# IC_Adapter_2x1x24.net
KiCad netlist of a schematic drawn in EAGLE
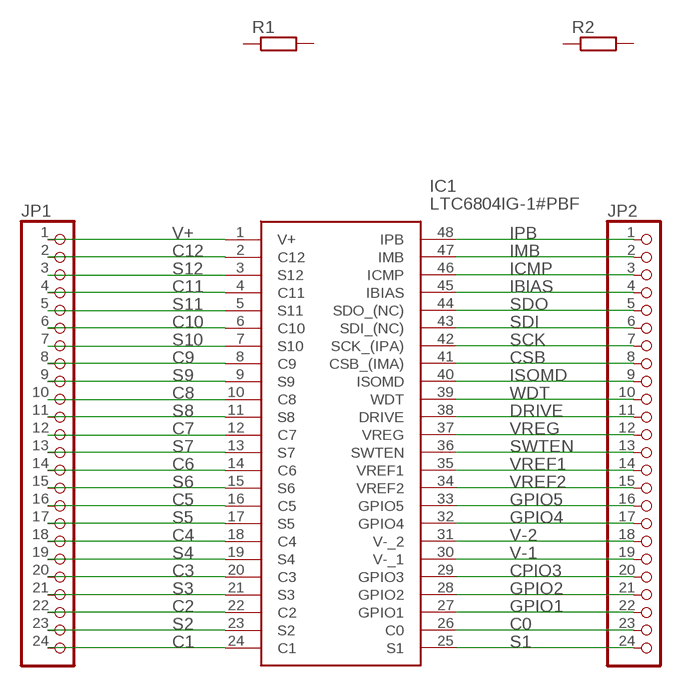
[diagram p0: schematic, sheet 1]

(export (version "E")
  (design (tool "Eeschema 10.0.6"))
  (components
    (comp (ref "IC1")
      (value "LTC6804IG-1#PBF")
      (footprint "eagle-import:SOP50P780X200-48N")
      (fields (field (name "MOUSER_PART_NUMBER") "584-LTC6804IG-1#PBF"))
      (libsource (lib "eagle-import") (part "LTC6804IG-1#PBF"))
    )
    (comp (ref "JP1")
      (value "PINHD-1X24")
      (footprint "eagle-import:1X24")
      (libsource (lib "eagle-import") (part "PINHD-1X24"))
    )
    (comp (ref "JP2")
      (value "PINHD-1X24")
      (footprint "eagle-import:1X24")
      (libsource (lib "eagle-import") (part "PINHD-1X24"))
    )
    (comp (ref "R1")
      (value "R-EU_R1210")
      (footprint "eagle-import:R1210")
      (libsource (lib "eagle-import") (part "R-EU_R1210"))
    )
    (comp (ref "R2")
      (value "R-EU_R1210")
      (footprint "eagle-import:R1210")
      (libsource (lib "eagle-import") (part "R-EU_R1210"))
    )
  )
  (nets
    (net (code "1") (name "/C0") (class "Default")
      (node (ref "IC1") (pin "26") (pinfunction "C0_26") (pintype "bidirectional"))
      (node (ref "JP2") (pin "23") (pinfunction "23_23") (pintype "passive"))
    )
    (net (code "2") (name "/C1") (class "Default")
      (node (ref "IC1") (pin "24") (pinfunction "C1_24") (pintype "bidirectional"))
      (node (ref "JP1") (pin "24") (pinfunction "24_24") (pintype "passive"))
    )
    (net (code "3") (name "/C2") (class "Default")
      (node (ref "IC1") (pin "22") (pinfunction "C2_22") (pintype "bidirectional"))
      (node (ref "JP1") (pin "22") (pinfunction "22_22") (pintype "passive"))
    )
    (net (code "4") (name "/C3") (class "Default")
      (node (ref "IC1") (pin "20") (pinfunction "C3_20") (pintype "bidirectional"))
      (node (ref "JP1") (pin "20") (pinfunction "20_20") (pintype "passive"))
    )
    (net (code "5") (name "/C4") (class "Default")
      (node (ref "IC1") (pin "18") (pinfunction "C4_18") (pintype "bidirectional"))
      (node (ref "JP1") (pin "18") (pinfunction "18_18") (pintype "passive"))
    )
    (net (code "6") (name "/C5") (class "Default")
      (node (ref "IC1") (pin "16") (pinfunction "C5_16") (pintype "bidirectional"))
      (node (ref "JP1") (pin "16") (pinfunction "16_16") (pintype "passive"))
    )
    (net (code "7") (name "/C6") (class "Default")
      (node (ref "IC1") (pin "14") (pinfunction "C6_14") (pintype "bidirectional"))
      (node (ref "JP1") (pin "14") (pinfunction "14_14") (pintype "passive"))
    )
    (net (code "8") (name "/C7") (class "Default")
      (node (ref "IC1") (pin "12") (pinfunction "C7_12") (pintype "bidirectional"))
      (node (ref "JP1") (pin "12") (pinfunction "12_12") (pintype "passive"))
    )
    (net (code "9") (name "/C8") (class "Default")
      (node (ref "IC1") (pin "10") (pinfunction "C8_10") (pintype "bidirectional"))
      (node (ref "JP1") (pin "10") (pinfunction "10_10") (pintype "passive"))
    )
    (net (code "10") (name "/C9") (class "Default")
      (node (ref "IC1") (pin "8") (pinfunction "C9_8") (pintype "bidirectional"))
      (node (ref "JP1") (pin "8") (pinfunction "8_8") (pintype "passive"))
    )
    (net (code "11") (name "/C10") (class "Default")
      (node (ref "IC1") (pin "6") (pinfunction "C10_6") (pintype "bidirectional"))
      (node (ref "JP1") (pin "6") (pinfunction "6_6") (pintype "passive"))
    )
    (net (code "12") (name "/C11") (class "Default")
      (node (ref "IC1") (pin "4") (pinfunction "C11_4") (pintype "bidirectional"))
      (node (ref "JP1") (pin "4") (pinfunction "4_4") (pintype "passive"))
    )
    (net (code "13") (name "/C12") (class "Default")
      (node (ref "IC1") (pin "2") (pinfunction "C12_2") (pintype "bidirectional"))
      (node (ref "JP1") (pin "2") (pinfunction "2_2") (pintype "passive"))
    )
    (net (code "14") (name "/CPIO3") (class "Default")
      (node (ref "IC1") (pin "29") (pinfunction "GPIO3_29") (pintype "bidirectional"))
      (node (ref "JP2") (pin "20") (pinfunction "20_20") (pintype "passive"))
    )
    (net (code "15") (name "/CSB") (class "Default")
      (node (ref "IC1") (pin "41") (pinfunction "CSB_(IMA)_41") (pintype "bidirectional"))
      (node (ref "JP2") (pin "8") (pinfunction "8_8") (pintype "passive"))
    )
    (net (code "16") (name "/DRIVE") (class "Default")
      (node (ref "IC1") (pin "38") (pinfunction "DRIVE_38") (pintype "bidirectional"))
      (node (ref "JP2") (pin "11") (pinfunction "11_11") (pintype "passive"))
    )
    (net (code "17") (name "/GPIO1") (class "Default")
      (node (ref "IC1") (pin "27") (pinfunction "GPIO1_27") (pintype "bidirectional"))
      (node (ref "JP2") (pin "22") (pinfunction "22_22") (pintype "passive"))
    )
    (net (code "18") (name "/GPIO2") (class "Default")
      (node (ref "IC1") (pin "28") (pinfunction "GPIO2_28") (pintype "bidirectional"))
      (node (ref "JP2") (pin "21") (pinfunction "21_21") (pintype "passive"))
    )
    (net (code "19") (name "/GPIO4") (class "Default")
      (node (ref "IC1") (pin "32") (pinfunction "GPIO4_32") (pintype "bidirectional"))
      (node (ref "JP2") (pin "17") (pinfunction "17_17") (pintype "passive"))
    )
    (net (code "20") (name "/GPIO5") (class "Default")
      (node (ref "IC1") (pin "33") (pinfunction "GPIO5_33") (pintype "bidirectional"))
      (node (ref "JP2") (pin "16") (pinfunction "16_16") (pintype "passive"))
    )
    (net (code "21") (name "/IBIAS") (class "Default")
      (node (ref "IC1") (pin "45") (pinfunction "IBIAS_45") (pintype "bidirectional"))
      (node (ref "JP2") (pin "4") (pinfunction "4_4") (pintype "passive"))
    )
    (net (code "22") (name "/ICMP") (class "Default")
      (node (ref "IC1") (pin "46") (pinfunction "ICMP_46") (pintype "bidirectional"))
      (node (ref "JP2") (pin "3") (pinfunction "3_3") (pintype "passive"))
    )
    (net (code "23") (name "/IMB") (class "Default")
      (node (ref "IC1") (pin "47") (pinfunction "IMB_47") (pintype "bidirectional"))
      (node (ref "JP2") (pin "2") (pinfunction "2_2") (pintype "passive"))
    )
    (net (code "24") (name "/IPB") (class "Default")
      (node (ref "IC1") (pin "48") (pinfunction "IPB_48") (pintype "bidirectional"))
      (node (ref "JP2") (pin "1") (pinfunction "1_1") (pintype "passive"))
    )
    (net (code "25") (name "/ISOMD") (class "Default")
      (node (ref "IC1") (pin "40") (pinfunction "ISOMD_40") (pintype "bidirectional"))
      (node (ref "JP2") (pin "9") (pinfunction "9_9") (pintype "passive"))
    )
    (net (code "26") (name "/S1") (class "Default")
      (node (ref "IC1") (pin "25") (pinfunction "S1_25") (pintype "bidirectional"))
      (node (ref "JP2") (pin "24") (pinfunction "24_24") (pintype "passive"))
    )
    (net (code "27") (name "/S2") (class "Default")
      (node (ref "IC1") (pin "23") (pinfunction "S2_23") (pintype "bidirectional"))
      (node (ref "JP1") (pin "23") (pinfunction "23_23") (pintype "passive"))
    )
    (net (code "28") (name "/S3") (class "Default")
      (node (ref "IC1") (pin "21") (pinfunction "S3_21") (pintype "bidirectional"))
      (node (ref "JP1") (pin "21") (pinfunction "21_21") (pintype "passive"))
    )
    (net (code "29") (name "/S4") (class "Default")
      (node (ref "IC1") (pin "19") (pinfunction "S4_19") (pintype "bidirectional"))
      (node (ref "JP1") (pin "19") (pinfunction "19_19") (pintype "passive"))
    )
    (net (code "30") (name "/S5") (class "Default")
      (node (ref "IC1") (pin "17") (pinfunction "S5_17") (pintype "bidirectional"))
      (node (ref "JP1") (pin "17") (pinfunction "17_17") (pintype "passive"))
    )
    (net (code "31") (name "/S6") (class "Default")
      (node (ref "IC1") (pin "15") (pinfunction "S6_15") (pintype "bidirectional"))
      (node (ref "JP1") (pin "15") (pinfunction "15_15") (pintype "passive"))
    )
    (net (code "32") (name "/S7") (class "Default")
      (node (ref "IC1") (pin "13") (pinfunction "S7_13") (pintype "bidirectional"))
      (node (ref "JP1") (pin "13") (pinfunction "13_13") (pintype "passive"))
    )
    (net (code "33") (name "/S8") (class "Default")
      (node (ref "IC1") (pin "11") (pinfunction "S8_11") (pintype "bidirectional"))
      (node (ref "JP1") (pin "11") (pinfunction "11_11") (pintype "passive"))
    )
    (net (code "34") (name "/S9") (class "Default")
      (node (ref "IC1") (pin "9") (pinfunction "S9_9") (pintype "bidirectional"))
      (node (ref "JP1") (pin "9") (pinfunction "9_9") (pintype "passive"))
    )
    (net (code "35") (name "/S10") (class "Default")
      (node (ref "IC1") (pin "7") (pinfunction "S10_7") (pintype "bidirectional"))
      (node (ref "JP1") (pin "7") (pinfunction "7_7") (pintype "passive"))
    )
    (net (code "36") (name "/S11") (class "Default")
      (node (ref "IC1") (pin "5") (pinfunction "S11_5") (pintype "bidirectional"))
      (node (ref "JP1") (pin "5") (pinfunction "5_5") (pintype "passive"))
    )
    (net (code "37") (name "/S12") (class "Default")
      (node (ref "IC1") (pin "3") (pinfunction "S12_3") (pintype "bidirectional"))
      (node (ref "JP1") (pin "3") (pinfunction "3_3") (pintype "passive"))
    )
    (net (code "38") (name "/SCK") (class "Default")
      (node (ref "IC1") (pin "42") (pinfunction "SCK_(IPA)_42") (pintype "bidirectional"))
      (node (ref "JP2") (pin "7") (pinfunction "7_7") (pintype "passive"))
    )
    (net (code "39") (name "/SDI") (class "Default")
      (node (ref "IC1") (pin "43") (pinfunction "SDI_(NC)_43") (pintype "bidirectional"))
      (node (ref "JP2") (pin "6") (pinfunction "6_6") (pintype "passive"))
    )
    (net (code "40") (name "/SDO") (class "Default")
      (node (ref "IC1") (pin "44") (pinfunction "SDO_(NC)_44") (pintype "bidirectional"))
      (node (ref "JP2") (pin "5") (pinfunction "5_5") (pintype "passive"))
    )
    (net (code "41") (name "/SWTEN") (class "Default")
      (node (ref "IC1") (pin "36") (pinfunction "SWTEN_36") (pintype "bidirectional"))
      (node (ref "JP2") (pin "13") (pinfunction "13_13") (pintype "passive"))
    )
    (net (code "42") (name "/V+") (class "Default")
      (node (ref "IC1") (pin "1") (pinfunction "V+_1") (pintype "bidirectional"))
      (node (ref "JP1") (pin "1") (pinfunction "1_1") (pintype "passive"))
    )
    (net (code "43") (name "/V-1") (class "Default")
      (node (ref "IC1") (pin "30") (pinfunction "V-_1_30") (pintype "bidirectional"))
      (node (ref "JP2") (pin "19") (pinfunction "19_19") (pintype "passive"))
    )
    (net (code "44") (name "/V-2") (class "Default")
      (node (ref "IC1") (pin "31") (pinfunction "V-_2_31") (pintype "bidirectional"))
      (node (ref "JP2") (pin "18") (pinfunction "18_18") (pintype "passive"))
    )
    (net (code "45") (name "/VREF1") (class "Default")
      (node (ref "IC1") (pin "35") (pinfunction "VREF1_35") (pintype "bidirectional"))
      (node (ref "JP2") (pin "14") (pinfunction "14_14") (pintype "passive"))
    )
    (net (code "46") (name "/VREF2") (class "Default")
      (node (ref "IC1") (pin "34") (pinfunction "VREF2_34") (pintype "bidirectional"))
      (node (ref "JP2") (pin "15") (pinfunction "15_15") (pintype "passive"))
    )
    (net (code "47") (name "/VREG") (class "Default")
      (node (ref "IC1") (pin "37") (pinfunction "VREG_37") (pintype "bidirectional"))
      (node (ref "JP2") (pin "12") (pinfunction "12_12") (pintype "passive"))
    )
    (net (code "48") (name "/WDT") (class "Default")
      (node (ref "IC1") (pin "39") (pinfunction "WDT_39") (pintype "bidirectional"))
      (node (ref "JP2") (pin "10") (pinfunction "10_10") (pintype "passive"))
    )
    (net (code "49") (name "unconnected-(R1-Pad1)") (class "Default")
      (node (ref "R1") (pin "1") (pinfunction "1_1") (pintype "passive"))
    )
    (net (code "50") (name "unconnected-(R1-Pad2)") (class "Default")
      (node (ref "R1") (pin "2") (pinfunction "2_2") (pintype "passive"))
    )
    (net (code "51") (name "unconnected-(R2-Pad1)") (class "Default")
      (node (ref "R2") (pin "1") (pinfunction "1_1") (pintype "passive"))
    )
    (net (code "52") (name "unconnected-(R2-Pad2)") (class "Default")
      (node (ref "R2") (pin "2") (pinfunction "2_2") (pintype "passive"))
    )
  )
)
